# main.net
KiCad netlist of a schematic drawn in Altium Designer
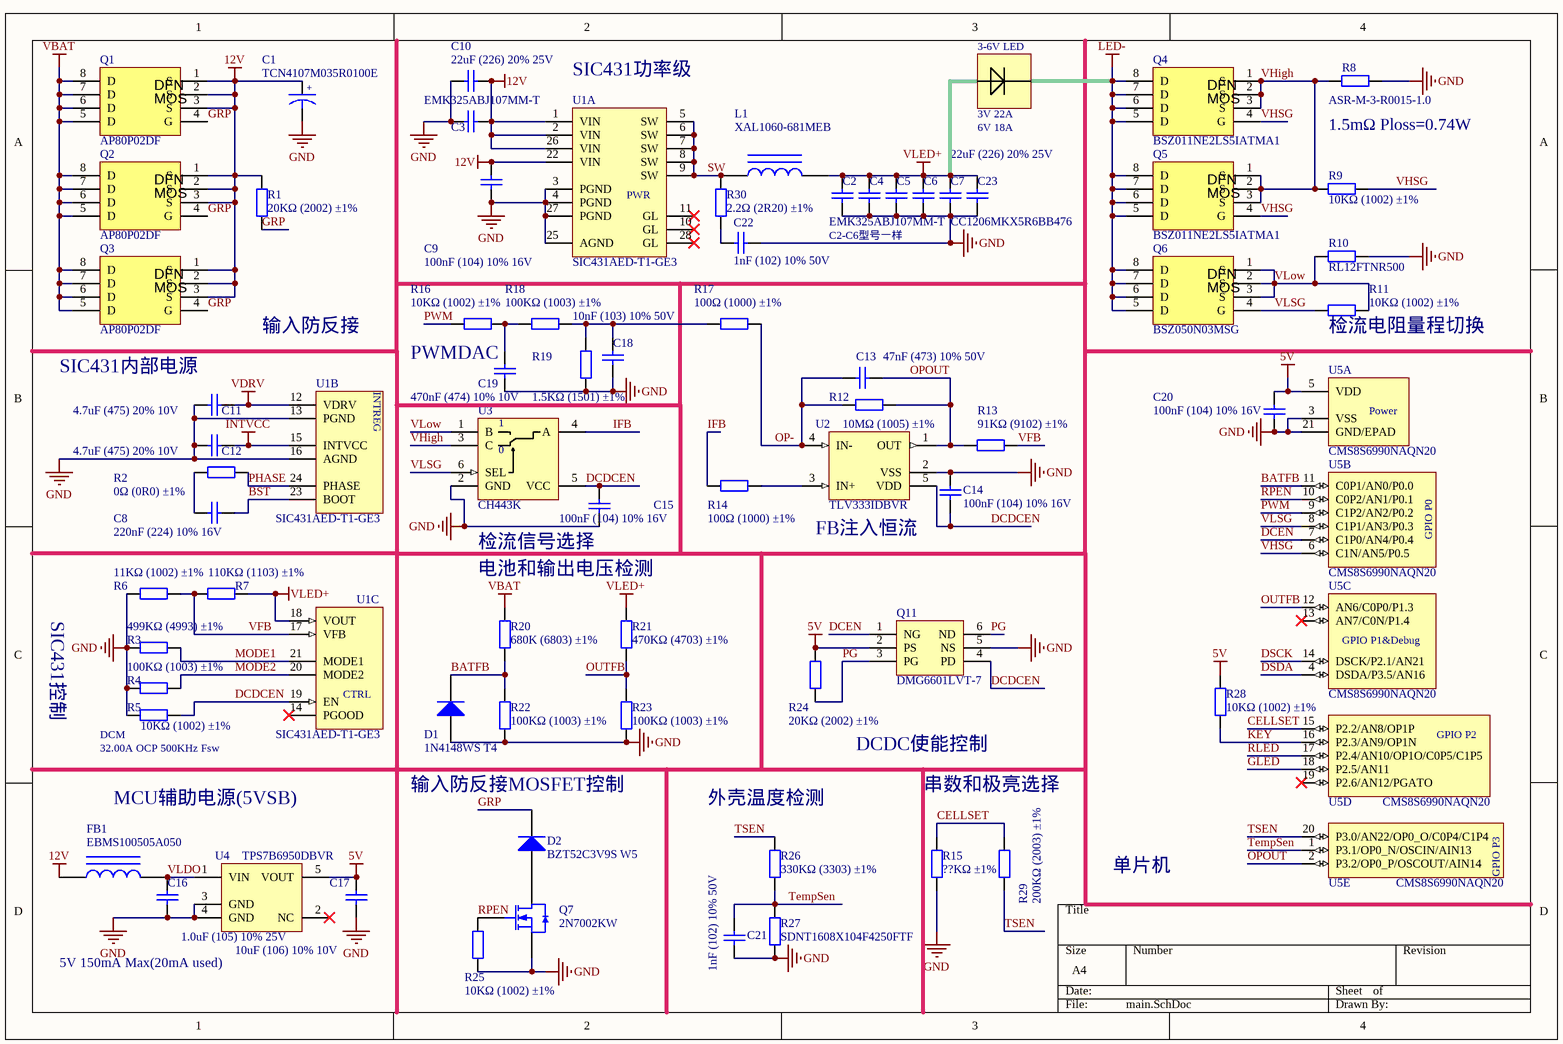
[diagram p0: main.SchDoc]

(export (version "E")
  (design (tool "Eeschema 10.0.6"))
  (components
    (comp (ref "C1")
      (value "TCN4107M035R0100E")
      (footprint "TCN4")
      (description "京瓷/AVX 贴片聚合物钽电容器 35V 100uF ±20% 2924 ESR=100mΩ")
      (libsource (lib "山猫的集成库20190318") (part "CAP2"))
    )
    (comp (ref "C2")
      (value "EMK325ABJ107MM-T")
      (footprint "1210C")
      (description "1210尺寸多层陶瓷电容器(MLCC) X5R材质，16V 100uF±20%")
      (fields (field (name "PUBLISHER") "Altium Limited"))
      (libsource (lib "山猫的集成库20190318") (part "Cap"))
    )
    (comp (ref "C3")
      (value "EMK325ABJ107MM-T")
      (footprint "1210C")
      (description "1210尺寸多层陶瓷电容器(MLCC) X5R材质，16V 100uF±20%")
      (fields (field (name "PUBLISHER") "Altium Limited"))
      (libsource (lib "山猫的集成库20190318") (part "Cap"))
    )
    (comp (ref "C4")
      (value "EMK325ABJ107MM-T")
      (footprint "1210C")
      (description "1210尺寸多层陶瓷电容器(MLCC) X5R材质，16V 100uF±20%")
      (fields (field (name "PUBLISHER") "Altium Limited"))
      (libsource (lib "山猫的集成库20190318") (part "Cap"))
    )
    (comp (ref "C5")
      (value "EMK325ABJ107MM-T")
      (footprint "1210C")
      (description "1210尺寸多层陶瓷电容器(MLCC) X5R材质，16V 100uF±20%")
      (fields (field (name "PUBLISHER") "Altium Limited"))
      (libsource (lib "山猫的集成库20190318") (part "Cap"))
    )
    (comp (ref "C6")
      (value "EMK325ABJ107MM-T")
      (footprint "1210C")
      (description "1210尺寸多层陶瓷电容器(MLCC) X5R材质，16V 100uF±20%")
      (fields (field (name "PUBLISHER") "Altium Limited"))
      (libsource (lib "山猫的集成库20190318") (part "Cap"))
    )
    (comp (ref "C7")
      (value "22uF (226) 20% 25V")
      (footprint "0805_C")
      (description "贴片电容")
      (libsource (lib "Miscellaneous Devices LC") (part "0805 22uF (226) 20% 25V"))
    )
    (comp (ref "C8")
      (value "220nF (224) 10% 16V")
      (footprint "0402_C")
      (description "贴片电容")
      (libsource (lib "Miscellaneous Devices LC") (part "0402 220nF (224) 10% 16V"))
    )
    (comp (ref "C9")
      (value "100nF (104) 10% 16V")
      (footprint "0402_C")
      (description "贴片电容")
      (libsource (lib "Miscellaneous Devices LC") (part "0402 100nF (104) 10% 16V"))
    )
    (comp (ref "C10")
      (value "22uF (226) 20% 25V")
      (footprint "0805_C")
      (description "贴片电容")
      (libsource (lib "Miscellaneous Devices LC") (part "0805 22uF (226) 20% 25V"))
    )
    (comp (ref "C11")
      (value "4.7uF (475) 20% 10V")
      (footprint "0402_C")
      (description "贴片电容")
      (libsource (lib "Miscellaneous Devices LC") (part "0402 4.7uF (475) 20% 10V"))
    )
    (comp (ref "C12")
      (value "4.7uF (475) 20% 10V")
      (footprint "0402_C")
      (description "贴片电容")
      (libsource (lib "Miscellaneous Devices LC") (part "0402 4.7uF (475) 20% 10V"))
    )
    (comp (ref "C13")
      (value "47nF (473) 10% 50V")
      (footprint "0402_C")
      (description "贴片电容")
      (libsource (lib "Miscellaneous Devices LC") (part "0402 100nF (104) 10% 16V"))
    )
    (comp (ref "C14")
      (value "100nF (104) 10% 16V")
      (footprint "0402_C")
      (description "贴片电容")
      (libsource (lib "Miscellaneous Devices LC") (part "0402 100nF (104) 10% 16V"))
    )
    (comp (ref "C15")
      (value "100nF (104) 10% 16V")
      (footprint "0402_C")
      (description "贴片电容")
      (libsource (lib "Miscellaneous Devices LC") (part "0402 100nF (104) 10% 16V"))
    )
    (comp (ref "C16")
      (value "1.0uF (105) 10% 25V")
      (footprint "0402_C")
      (description "贴片电容")
      (libsource (lib "Miscellaneous Devices LC") (part "0402 1.0uF (105) 10% 25V"))
    )
    (comp (ref "C17")
      (value "10uF (106) 10% 10V")
      (footprint "0603_C")
      (description "贴片电容")
      (libsource (lib "Miscellaneous Devices LC") (part "0603 10uF (106) 10% 10V"))
    )
    (comp (ref "C18")
      (value "10nF (103) 10% 50V")
      (footprint "0402_C")
      (description "贴片电容")
      (libsource (lib "Miscellaneous Devices LC") (part "0402 10nF (103) 10% 50V"))
    )
    (comp (ref "C19")
      (value "470nF (474) 10% 10V")
      (footprint "0402_C")
      (description "贴片电容")
      (libsource (lib "Miscellaneous Devices LC") (part "0402 470nF (474) 10% 10V"))
    )
    (comp (ref "C20")
      (value "100nF (104) 10% 16V")
      (footprint "0402_C")
      (description "贴片电容")
      (libsource (lib "Miscellaneous Devices LC") (part "0402 100nF (104) 10% 16V"))
    )
    (comp (ref "C21")
      (value "1nF (102) 10% 50V")
      (footprint "0402_C")
      (description "贴片电容")
      (libsource (lib "Miscellaneous Devices LC") (part "0402 1nF (102) 10% 50V"))
    )
    (comp (ref "C22")
      (value "1nF (102) 10% 50V")
      (footprint "0402_C")
      (description "贴片电容")
      (libsource (lib "Miscellaneous Devices LC") (part "0402 1nF (102) 10% 50V"))
    )
    (comp (ref "C23")
      (value "CC1206MKX5R6BB476")
      (footprint "1206C")
      (description "1206 MLCC电容 10V 47uF±20% X5R")
      (fields (field (name "PUBLISHER") "Altium Limited"))
      (libsource (lib "山猫的集成库20190318") (part "Cap"))
    )
    (comp (ref "D1")
      (value "1N4148WS T4")
      (footprint "SOD-323")
      (description "二极管")
      (libsource (lib "Miscellaneous Devices LC") (part "SOD-323 1N4148WS T4"))
    )
    (comp (ref "D2")
      (value "BZT52C3V9S W5")
      (footprint "SOD-323")
      (description "SOD-323封装贴片稳压二极管，3.9V 200mW")
      (libsource (lib "Miscellaneous Devices LC") (part "SOD-323 1N4148WS T4"))
    )
    (comp (ref "FB1")
      (value "EBMS100505A050")
      (footprint "0402_L")
      (description "贴片磁珠 200mA 5R±25% 100MHz")
      (libsource (lib "Miscellaneous Devices LC") (part "0402 12nH  5%"))
    )
    (comp (ref "L1")
      (value "XAL1060-681MEB")
      (footprint "XAL1010-XXXME")
      (description "Coilcraft Inductor XAL1070 Series")
      (fields (field (name "PUBLISHER") "Altium Limited"))
      (libsource (lib "Miscellaneous Devices") (part "Inductor Iron"))
    )
    (comp (ref "Q1")
      (value "AP80P02DF")
      (footprint "DFN-8_L3.0-W3.0-P0.65-BL")
      (description "永源微 PDFN3x3-8L -20V -80A 4.0mΩ P沟道MOSFET")
      (libsource (lib "custom") (part "SON/DFN5x6 MOS"))
    )
    (comp (ref "Q2")
      (value "AP80P02DF")
      (footprint "DFN-8_L3.0-W3.0-P0.65-BL")
      (description "永源微 PDFN3x3-8L -20V -80A 4.0mΩ P沟道MOSFET")
      (libsource (lib "custom") (part "SON/DFN5x6 MOS"))
    )
    (comp (ref "Q3")
      (value "AP80P02DF")
      (footprint "DFN-8_L3.0-W3.0-P0.65-BL")
      (description "永源微 PDFN3x3-8L -20V -80A 4.0mΩ P沟道MOSFET")
      (libsource (lib "custom") (part "SON/DFN5x6 MOS"))
    )
    (comp (ref "Q4")
      (value "BSZ011NE2LS5IATMA1")
      (footprint "DFN-8_L3.0-W3.0-P0.65-BL")
      (description "PDFN3x3 37nC 25V 40A 1.1mΩ OptiMOS-5 N沟道MOSFET")
      (libsource (lib "custom") (part "SON/DFN5x6 MOS"))
    )
    (comp (ref "Q5")
      (value "BSZ011NE2LS5IATMA1")
      (footprint "DFN-8_L3.0-W3.0-P0.65-BL")
      (description "PDFN3x3 37nC 25V 40A 1.1mΩ OptiMOS-5 N沟道MOSFET")
      (libsource (lib "custom") (part "SON/DFN5x6 MOS"))
    )
    (comp (ref "Q6")
      (value "BSZ050N03MSG")
      (footprint "DFN-8_L3.0-W3.0-P0.65-BL")
      (description "PDFN3x3 30V 45A 4.6mΩ OptiMOS-3 N沟道MOSFET")
      (libsource (lib "custom") (part "SON/DFN5x6 MOS"))
    )
    (comp (ref "Q7")
      (value "2N7002KW")
      (footprint "SC70-3")
      (description "单N沟道MOSFET(场效应管)")
      (libsource (lib "Miscellaneous Devices LC") (part "2N7002 7002"))
    )
    (comp (ref "Q11")
      (value "DMG6601LVT-7")
      (footprint "SOT95P245X110-6N")
      (description "SOT23-6 N+P Ch. MOSFET")
      (libsource (lib "custom") (part "DMG6601LVT"))
    )
    (comp (ref "R1")
      (value "20KΩ (2002) ±1%")
      (footprint "0402_R")
      (description "贴片电阻")
      (libsource (lib "Miscellaneous Devices LC") (part "0402 20KΩ (2002) 1%"))
    )
    (comp (ref "R2")
      (value "0Ω (0R0) ±1%")
      (footprint "0402_R")
      (description "贴片电阻")
      (libsource (lib "Miscellaneous Devices LC") (part "0402 0Ω (0R0) 1%"))
    )
    (comp (ref "R3")
      (value "499KΩ (4993) ±1%")
      (footprint "0402_R")
      (description "贴片电阻")
      (libsource (lib "") (part "0402 100KΩ (1003) 1%_1"))
    )
    (comp (ref "R4")
      (value "100KΩ (1003) ±1%")
      (footprint "0402_R")
      (description "贴片电阻")
      (libsource (lib "") (part "0402 100KΩ (1003) 1%_1"))
    )
    (comp (ref "R5")
      (value "10KΩ (1002) ±1%")
      (footprint "0402_R")
      (description "贴片电阻")
      (libsource (lib "Miscellaneous Devices LC") (part "0402 10KΩ (1002) 1%"))
    )
    (comp (ref "R6")
      (value "11KΩ (1002) ±1%")
      (footprint "0402_R")
      (description "贴片电阻")
      (libsource (lib "") (part "0402 10KΩ (1002) 1%_1"))
    )
    (comp (ref "R7")
      (value "110KΩ (1103) ±1%")
      (footprint "0402_R")
      (description "贴片电阻")
      (libsource (lib "") (part "0402 10KΩ (1002) 1%_1"))
    )
    (comp (ref "R8")
      (value "ASR-M-3-R0015-1.0")
      (footprint "2512")
      (description "深圳华讯高科精密检流电阻，2512 1.5mΩ±1% 卡玛材质 <50ppm/K P70℃=3W")
      (fields (field (name "PUBLISHER") "Altium Limited"))
      (libsource (lib "山猫的集成库20190318") (part "Res"))
    )
    (comp (ref "R9")
      (value "10KΩ (1002) ±1%")
      (footprint "0402_R")
      (description "贴片电阻")
      (libsource (lib "Miscellaneous Devices LC") (part "0402 10KΩ (1002) 1%"))
    )
    (comp (ref "R10")
      (value "RL12FTNR500")
      (footprint "1206R")
      (description "1206厚膜采样电阻 0.5Ω ±1% 1/2W")
      (fields (field (name "PUBLISHER") "Altium Limited"))
      (libsource (lib "山猫的集成库20190318") (part "Res"))
    )
    (comp (ref "R11")
      (value "10KΩ (1002) ±1%")
      (footprint "0402_R")
      (description "贴片电阻")
      (libsource (lib "Miscellaneous Devices LC") (part "0402 10KΩ (1002) 1%"))
    )
    (comp (ref "R12")
      (value "10MΩ (1005) ±1%")
      (footprint "0402_R")
      (description "贴片电阻")
      (libsource (lib "Miscellaneous Devices LC") (part "0402 1MΩ (1004) 1%"))
    )
    (comp (ref "R13")
      (value "91KΩ (9102) ±1%")
      (footprint "0402_R")
      (description "贴片电阻")
      (libsource (lib "") (part "0402 100KΩ (1003) 1%_1"))
    )
    (comp (ref "R14")
      (value "100Ω (1000) ±1%")
      (footprint "0402_R")
      (description "贴片电阻")
      (libsource (lib "Miscellaneous Devices LC") (part "0402 470Ω (4700) 1%"))
    )
    (comp (ref "R15")
      (value "??KΩ ±1%")
      (footprint "0603_R")
      (description "贴片电阻")
      (libsource (lib "Miscellaneous Devices LC") (part "0603 10KΩ (1002) 1%"))
    )
    (comp (ref "R16")
      (value "10KΩ (1002) ±1%")
      (footprint "0402_R")
      (description "贴片电阻")
      (libsource (lib "Miscellaneous Devices LC") (part "0402 10KΩ (1002) 1%"))
    )
    (comp (ref "R17")
      (value "100Ω (1000) ±1%")
      (footprint "0402_R")
      (description "贴片电阻")
      (libsource (lib "Miscellaneous Devices LC") (part "0402 470Ω (4700) 1%"))
    )
    (comp (ref "R18")
      (value "100KΩ (1003) ±1%")
      (footprint "0402_R")
      (description "贴片电阻")
      (libsource (lib "") (part "0402 100KΩ (1003) 1%_1"))
    )
    (comp (ref "R19")
      (value "1.5KΩ (1501) ±1%")
      (footprint "0402_R")
      (description "贴片电阻")
      (libsource (lib "Miscellaneous Devices LC") (part "0402 1.5KΩ (1501) 1%"))
    )
    (comp (ref "R20")
      (value "680K (6803) ±1%")
      (footprint "0402_R")
      (description "贴片电阻")
      (libsource (lib "Miscellaneous Devices LC") (part "0402 680Ω (6800) 1%"))
    )
    (comp (ref "R21")
      (value "470KΩ (4703) ±1%")
      (footprint "0402_R")
      (description "贴片电阻")
      (libsource (lib "Miscellaneous Devices LC") (part "0402 470KΩ (4703) 1%"))
    )
    (comp (ref "R22")
      (value "100KΩ (1003) ±1%")
      (footprint "0402_R")
      (description "贴片电阻")
      (libsource (lib "Miscellaneous Devices LC") (part "0402 100KΩ (1003) 1%"))
    )
    (comp (ref "R23")
      (value "100KΩ (1003) ±1%")
      (footprint "0402_R")
      (description "贴片电阻")
      (libsource (lib "Miscellaneous Devices LC") (part "0402 100KΩ (1003) 1%"))
    )
    (comp (ref "R24")
      (value "20KΩ (2002) ±1%")
      (footprint "0402_R")
      (description "贴片电阻")
      (libsource (lib "Miscellaneous Devices LC") (part "0402 20KΩ (2002) 1%"))
    )
    (comp (ref "R25")
      (value "10KΩ (1002) ±1%")
      (footprint "0402_R")
      (description "贴片电阻")
      (libsource (lib "") (part "0402 10KΩ (1002) 1%_2"))
    )
    (comp (ref "R26")
      (value "330KΩ (3303) ±1%")
      (footprint "0402_R")
      (description "贴片电阻")
      (libsource (lib "Miscellaneous Devices LC") (part "0402 330KΩ (3303) 1%"))
    )
    (comp (ref "R27")
      (value "SDNT1608X104F4250FTF")
      (footprint "0603_R")
      (description "0603贴片NTC热敏电阻，100KΩ (1003) ±1% B4250")
      (libsource (lib "Miscellaneous Devices LC") (part "0603 100KΩ (1003) 1%"))
    )
    (comp (ref "R28")
      (value "10KΩ (1002) ±1%")
      (footprint "0402_R")
      (description "贴片电阻")
      (libsource (lib "") (part "0402 10KΩ (1002) 1%_2"))
    )
    (comp (ref "R29")
      (value "200KΩ (2003) ±1%")
      (footprint "0402_R")
      (description "贴片电阻")
      (libsource (lib "Miscellaneous Devices LC") (part "0402 100KΩ (1003) 1%"))
    )
    (comp (ref "R30")
      (value "2.2Ω (2R20) ±1%")
      (footprint "0805_R")
      (description "贴片电阻")
      (libsource (lib "Miscellaneous Devices LC") (part "0805 1Ω (1R00) 1%"))
    )
    (comp (ref "U1")
      (value "SIC431AED-T1-GE3")
      (footprint "QFN_ED-T1-GE3_VIS")
      (description "3 to 24V Input 24A MicroBuck DCDC Converter with bulit-in MOSFET")
      (libsource (lib "custom") (part "SIC431AED-T1-GE3"))
    )
    (comp (ref "U2")
      (value "TLV333IDBVR")
      (footprint "SOT95P245X110-5N")
      (description "低噪声轨到轨输入输出精密运放 350Khz")
      (libsource (lib "custom") (part "TLV333IDBVR"))
    )
    (comp (ref "U3")
      (value "CH443K")
      (footprint "SC70-6")
      (description "Low-Voltage Analog Switch SPDT,1.8-5V Power")
      (libsource (lib "custom") (part "NC7SB3157P6X"))
    )
    (comp (ref "U4")
      (value "TPS7B6950DBVR")
      (footprint "SOT95P245X110-5N")
      (description "150mA 40V max input Ultra low Iq LDO,fixed 5V output")
      (libsource (lib "custom") (part "TPS7B6933DBVR"))
    )
    (comp (ref "U5")
      (value "CMS8S6990NAQN20")
      (footprint "QFN40P300X300X800_HS-21N")
      (description "增强型闪存1T 8051单片机，16KB Flash 256+1K XRAM")
      (libsource (lib "custom") (part "CM8S6990NA-QFN20"))
    )
  )
  (nets
    (net (code "1") (name "/BATFB") (class "Default")
      (node (ref "D1") (pin "2") (pinfunction "K_2") (pintype "passive"))
      (node (ref "R20") (pin "1") (pinfunction "1_1") (pintype "passive"))
      (node (ref "R22") (pin "2") (pinfunction "2_2") (pintype "passive"))
      (node (ref "U5") (pin "11") (pinfunction "C0P1/AN0/P0.0_11") (pintype "bidirectional"))
    )
    (net (code "2") (name "/BST") (class "Default")
      (node (ref "C8") (pin "2") (pinfunction "2_2") (pintype "passive"))
      (node (ref "U1") (pin "23") (pinfunction "BOOT_23") (pintype "power_in"))
    )
    (net (code "3") (name "/CELLSET") (class "Default")
      (node (ref "R15") (pin "2") (pinfunction "2_2") (pintype "passive"))
      (node (ref "R29") (pin "2") (pinfunction "2_2") (pintype "passive"))
      (node (ref "U5") (pin "15") (pinfunction "P2.2/AN8/OP1P_15") (pintype "bidirectional"))
    )
    (net (code "4") (name "/DCDCEN") (class "Default")
      (node (ref "C14") (pin "1") (pinfunction "1_1") (pintype "passive"))
      (node (ref "C15") (pin "2") (pinfunction "2_2") (pintype "passive"))
      (node (ref "Q11") (pin "4") (pinfunction "PD_4") (pintype "passive"))
      (node (ref "R5") (pin "2") (pinfunction "2_2") (pintype "passive"))
      (node (ref "U1") (pin "19") (pinfunction "EN_19") (pintype "input"))
      (node (ref "U2") (pin "5") (pinfunction "VDD_5") (pintype "power_in"))
      (node (ref "U3") (pin "5") (pinfunction "VCC_5") (pintype "power_in"))
    )
    (net (code "5") (name "/DCEN") (class "Default")
      (node (ref "Q11") (pin "1") (pinfunction "NG_1") (pintype "passive"))
      (node (ref "U5") (pin "7") (pinfunction "C1P0/AN4/P0.4_7") (pintype "bidirectional"))
    )
    (net (code "6") (name "/DSCK") (class "Default")
      (node (ref "U5") (pin "14") (pinfunction "DSCK/P2.1/AN21_14") (pintype "bidirectional"))
    )
    (net (code "7") (name "/DSDA") (class "Default")
      (node (ref "U5") (pin "4") (pinfunction "DSDA/P3.5/AN16_4") (pintype "bidirectional"))
    )
    (net (code "8") (name "/GLED") (class "Default")
      (node (ref "U5") (pin "18") (pinfunction "P2.5/AN11_18") (pintype "bidirectional"))
    )
    (net (code "9") (name "/GRP") (class "Default")
      (node (ref "D2") (pin "2") (pinfunction "K_2") (pintype "passive"))
      (node (ref "Q1") (pin "4") (pinfunction "G_4") (pintype "passive"))
      (node (ref "Q2") (pin "4") (pinfunction "G_4") (pintype "passive"))
      (node (ref "Q3") (pin "4") (pinfunction "G_4") (pintype "passive"))
      (node (ref "R1") (pin "1") (pinfunction "1_1") (pintype "passive"))
    )
    (net (code "10") (name "/IFB") (class "Default")
      (node (ref "R14") (pin "1") (pinfunction "1_1") (pintype "passive"))
      (node (ref "U3") (pin "4") (pinfunction "A_4") (pintype "passive"))
    )
    (net (code "11") (name "/KEY") (class "Default")
      (node (ref "R28") (pin "1") (pinfunction "1_1") (pintype "passive"))
      (node (ref "U5") (pin "16") (pinfunction "P2.3/AN9/OP1N_16") (pintype "bidirectional"))
    )
    (net (code "12") (name "/MODE1") (class "Default")
      (node (ref "R3") (pin "2") (pinfunction "2_2") (pintype "passive"))
      (node (ref "U1") (pin "21") (pinfunction "MODE1_21") (pintype "passive"))
    )
    (net (code "13") (name "/MODE2") (class "Default")
      (node (ref "R4") (pin "2") (pinfunction "2_2") (pintype "passive"))
      (node (ref "U1") (pin "20") (pinfunction "MODE2_20") (pintype "passive"))
    )
    (net (code "14") (name "/OP-") (class "Default")
      (node (ref "C13") (pin "1") (pinfunction "1_1") (pintype "passive"))
      (node (ref "R12") (pin "1") (pinfunction "1_1") (pintype "passive"))
      (node (ref "R17") (pin "2") (pinfunction "2_2") (pintype "passive"))
      (node (ref "U2") (pin "4") (pinfunction "IN-_4") (pintype "input"))
    )
    (net (code "15") (name "/OPOUT") (class "Default")
      (node (ref "C13") (pin "2") (pinfunction "2_2") (pintype "passive"))
      (node (ref "R12") (pin "2") (pinfunction "2_2") (pintype "passive"))
      (node (ref "R13") (pin "1") (pinfunction "1_1") (pintype "passive"))
      (node (ref "U2") (pin "1") (pinfunction "OUT_1") (pintype "output"))
      (node (ref "U5") (pin "2") (pinfunction "P3.2/OP0_P/OSCOUT/AIN14_2") (pintype "bidirectional"))
    )
    (net (code "16") (name "/OUTFB") (class "Default")
      (node (ref "R21") (pin "1") (pinfunction "1_1") (pintype "passive"))
      (node (ref "R23") (pin "2") (pinfunction "2_2") (pintype "passive"))
      (node (ref "U5") (pin "12") (pinfunction "AN6/C0P0/P1.3_12") (pintype "bidirectional"))
    )
    (net (code "17") (name "/PG") (class "Default")
      (node (ref "Q11") (pin "3") (pinfunction "PG_3") (pintype "passive"))
      (node (ref "Q11") (pin "6") (pinfunction "ND_6") (pintype "passive"))
      (node (ref "R24") (pin "1") (pinfunction "1_1") (pintype "passive"))
    )
    (net (code "18") (name "/PHASE") (class "Default")
      (node (ref "R2") (pin "2") (pinfunction "2_2") (pintype "passive"))
      (node (ref "U1") (pin "24") (pinfunction "PHASE_24") (pintype "power_in"))
    )
    (net (code "19") (name "/PWM") (class "Default")
      (node (ref "R16") (pin "1") (pinfunction "1_1") (pintype "passive"))
      (node (ref "U5") (pin "9") (pinfunction "C1P2/AN2/P0.2_9") (pintype "bidirectional"))
    )
    (net (code "20") (name "/RLED") (class "Default")
      (node (ref "U5") (pin "17") (pinfunction "P2.4/AN10/OP1O/C0P5/C1P5_17") (pintype "bidirectional"))
    )
    (net (code "21") (name "/RPEN") (class "Default")
      (node (ref "Q7") (pin "1") (pinfunction "G_1") (pintype "passive"))
      (node (ref "R25") (pin "2") (pinfunction "2_2") (pintype "passive"))
      (node (ref "U5") (pin "10") (pinfunction "C0P2/AN1/P0.1_10") (pintype "bidirectional"))
    )
    (net (code "22") (name "/SW") (class "Default")
      (node (ref "L1") (pin "1") (pinfunction "1_1") (pintype "passive"))
      (node (ref "R30") (pin "2") (pinfunction "2_2") (pintype "passive"))
      (node (ref "U1") (pin "5") (pinfunction "SW_5") (pintype "power_in"))
      (node (ref "U1") (pin "6") (pinfunction "SW_6") (pintype "power_in"))
      (node (ref "U1") (pin "7") (pinfunction "SW_7") (pintype "power_in"))
      (node (ref "U1") (pin "8") (pinfunction "SW_8") (pintype "power_in"))
      (node (ref "U1") (pin "9") (pinfunction "SW_9") (pintype "power_in"))
    )
    (net (code "23") (name "/TSEN") (class "Default")
      (node (ref "R26") (pin "2") (pinfunction "2_2") (pintype "passive"))
      (node (ref "R29") (pin "1") (pinfunction "1_1") (pintype "passive"))
      (node (ref "U5") (pin "20") (pinfunction "P3.0/AN22/OP0_O/C0P4/C1P4_20") (pintype "bidirectional"))
    )
    (net (code "24") (name "/TempSen") (class "Default")
      (node (ref "C21") (pin "2") (pinfunction "2_2") (pintype "passive"))
      (node (ref "R26") (pin "1") (pinfunction "1_1") (pintype "passive"))
      (node (ref "R27") (pin "1") (pinfunction "1_1") (pintype "passive"))
      (node (ref "U5") (pin "1") (pinfunction "P3.1/OP0_N/OSCIN/AIN13_1") (pintype "bidirectional"))
    )
    (net (code "25") (name "/VFB") (class "Default")
      (node (ref "R13") (pin "2") (pinfunction "2_2") (pintype "passive"))
      (node (ref "R6") (pin "1") (pinfunction "1_1") (pintype "passive"))
      (node (ref "R7") (pin "2") (pinfunction "2_2") (pintype "passive"))
      (node (ref "U1") (pin "17") (pinfunction "VFB_17") (pintype "input"))
    )
    (net (code "26") (name "/VHSG") (class "Default")
      (node (ref "Q4") (pin "4") (pinfunction "G_4") (pintype "passive"))
      (node (ref "Q5") (pin "4") (pinfunction "G_4") (pintype "passive"))
      (node (ref "R9") (pin "2") (pinfunction "2_2") (pintype "passive"))
      (node (ref "U5") (pin "6") (pinfunction "C1N/AN5/P0.5_6") (pintype "bidirectional"))
    )
    (net (code "27") (name "/VHigh") (class "Default")
      (node (ref "Q4") (pin "1") (pinfunction "S_1") (pintype "passive"))
      (node (ref "Q4") (pin "2") (pinfunction "S_2") (pintype "passive"))
      (node (ref "Q4") (pin "3") (pinfunction "S_3") (pintype "passive"))
      (node (ref "Q5") (pin "1") (pinfunction "S_1") (pintype "passive"))
      (node (ref "Q5") (pin "2") (pinfunction "S_2") (pintype "passive"))
      (node (ref "Q5") (pin "3") (pinfunction "S_3") (pintype "passive"))
      (node (ref "R8") (pin "2") (pinfunction "2_2") (pintype "passive"))
      (node (ref "R9") (pin "1") (pinfunction "1_1") (pintype "passive"))
      (node (ref "U3") (pin "3") (pinfunction "C_3") (pintype "passive"))
    )
    (net (code "28") (name "/VLDO") (class "Default")
      (node (ref "C16") (pin "2") (pinfunction "2_2") (pintype "passive"))
      (node (ref "FB1") (pin "2") (pinfunction "2_2") (pintype "passive"))
      (node (ref "U4") (pin "1") (pinfunction "VIN_1") (pintype "power_in"))
    )
    (net (code "29") (name "/VLSG") (class "Default")
      (node (ref "Q6") (pin "4") (pinfunction "G_4") (pintype "passive"))
      (node (ref "R11") (pin "1") (pinfunction "1_1") (pintype "passive"))
      (node (ref "U3") (pin "6") (pinfunction "SEL_6") (pintype "input"))
      (node (ref "U5") (pin "8") (pinfunction "C1P1/AN3/P0.3_8") (pintype "bidirectional"))
    )
    (net (code "30") (name "/VLow") (class "Default")
      (node (ref "Q6") (pin "1") (pinfunction "S_1") (pintype "passive"))
      (node (ref "Q6") (pin "2") (pinfunction "S_2") (pintype "passive"))
      (node (ref "Q6") (pin "3") (pinfunction "S_3") (pintype "passive"))
      (node (ref "R10") (pin "2") (pinfunction "2_2") (pintype "passive"))
      (node (ref "R11") (pin "2") (pinfunction "2_2") (pintype "passive"))
      (node (ref "U3") (pin "1") (pinfunction "B_1") (pintype "passive"))
    )
    (net (code "31") (name "5V") (class "Default")
      (node (ref "C17") (pin "2") (pinfunction "2_2") (pintype "passive"))
      (node (ref "C20") (pin "2") (pinfunction "2_2") (pintype "passive"))
      (node (ref "Q11") (pin "2") (pinfunction "PS_2") (pintype "passive"))
      (node (ref "R24") (pin "2") (pinfunction "2_2") (pintype "passive"))
      (node (ref "R28") (pin "2") (pinfunction "2_2") (pintype "passive"))
      (node (ref "U4") (pin "5") (pinfunction "VOUT_5") (pintype "power_in"))
      (node (ref "U5") (pin "5") (pinfunction "VDD_5") (pintype "power_in"))
    )
    (net (code "32") (name "12V") (class "Default")
      (node (ref "C1") (pin "1") (pinfunction "1_1") (pintype "passive"))
      (node (ref "C10") (pin "2") (pinfunction "2_2") (pintype "passive"))
      (node (ref "C3") (pin "2") (pinfunction "2_2") (pintype "passive"))
      (node (ref "C9") (pin "2") (pinfunction "2_2") (pintype "passive"))
      (node (ref "FB1") (pin "1") (pinfunction "1_1") (pintype "passive"))
      (node (ref "Q1") (pin "1") (pinfunction "S_1") (pintype "passive"))
      (node (ref "Q1") (pin "2") (pinfunction "S_2") (pintype "passive"))
      (node (ref "Q1") (pin "3") (pinfunction "S_3") (pintype "passive"))
      (node (ref "Q2") (pin "1") (pinfunction "S_1") (pintype "passive"))
      (node (ref "Q2") (pin "2") (pinfunction "S_2") (pintype "passive"))
      (node (ref "Q2") (pin "3") (pinfunction "S_3") (pintype "passive"))
      (node (ref "Q3") (pin "1") (pinfunction "S_1") (pintype "passive"))
      (node (ref "Q3") (pin "2") (pinfunction "S_2") (pintype "passive"))
      (node (ref "Q3") (pin "3") (pinfunction "S_3") (pintype "passive"))
      (node (ref "R1") (pin "2") (pinfunction "2_2") (pintype "passive"))
      (node (ref "U1") (pin "1") (pinfunction "VIN_1") (pintype "power_in"))
      (node (ref "U1") (pin "2") (pinfunction "VIN_2") (pintype "power_in"))
      (node (ref "U1") (pin "22") (pinfunction "VIN_22") (pintype "power_in"))
      (node (ref "U1") (pin "26") (pinfunction "VIN_26") (pintype "power_in"))
    )
    (net (code "33") (name "GND") (class "Default")
      (node (ref "C1") (pin "2") (pinfunction "2_2") (pintype "passive"))
      (node (ref "C10") (pin "1") (pinfunction "1_1") (pintype "passive"))
      (node (ref "C11") (pin "1") (pinfunction "1_1") (pintype "passive"))
      (node (ref "C12") (pin "1") (pinfunction "1_1") (pintype "passive"))
      (node (ref "C14") (pin "2") (pinfunction "2_2") (pintype "passive"))
      (node (ref "C15") (pin "1") (pinfunction "1_1") (pintype "passive"))
      (node (ref "C16") (pin "1") (pinfunction "1_1") (pintype "passive"))
      (node (ref "C17") (pin "1") (pinfunction "1_1") (pintype "passive"))
      (node (ref "C18") (pin "1") (pinfunction "1_1") (pintype "passive"))
      (node (ref "C19") (pin "1") (pinfunction "1_1") (pintype "passive"))
      (node (ref "C2") (pin "1") (pinfunction "1_1") (pintype "passive"))
      (node (ref "C20") (pin "1") (pinfunction "1_1") (pintype "passive"))
      (node (ref "C21") (pin "1") (pinfunction "1_1") (pintype "passive"))
      (node (ref "C22") (pin "1") (pinfunction "1_1") (pintype "passive"))
      (node (ref "C23") (pin "1") (pinfunction "1_1") (pintype "passive"))
      (node (ref "C3") (pin "1") (pinfunction "1_1") (pintype "passive"))
      (node (ref "C4") (pin "1") (pinfunction "1_1") (pintype "passive"))
      (node (ref "C5") (pin "1") (pinfunction "1_1") (pintype "passive"))
      (node (ref "C6") (pin "1") (pinfunction "1_1") (pintype "passive"))
      (node (ref "C7") (pin "1") (pinfunction "1_1") (pintype "passive"))
      (node (ref "C9") (pin "1") (pinfunction "1_1") (pintype "passive"))
      (node (ref "D1") (pin "1") (pinfunction "A_1") (pintype "passive"))
      (node (ref "Q11") (pin "5") (pinfunction "NS_5") (pintype "passive"))
      (node (ref "Q7") (pin "2") (pinfunction "S_2") (pintype "passive"))
      (node (ref "R10") (pin "1") (pinfunction "1_1") (pintype "passive"))
      (node (ref "R15") (pin "1") (pinfunction "1_1") (pintype "passive"))
      (node (ref "R19") (pin "1") (pinfunction "1_1") (pintype "passive"))
      (node (ref "R22") (pin "1") (pinfunction "1_1") (pintype "passive"))
      (node (ref "R23") (pin "1") (pinfunction "1_1") (pintype "passive"))
      (node (ref "R25") (pin "1") (pinfunction "1_1") (pintype "passive"))
      (node (ref "R27") (pin "2") (pinfunction "2_2") (pintype "passive"))
      (node (ref "R3") (pin "1") (pinfunction "1_1") (pintype "passive"))
      (node (ref "R4") (pin "1") (pinfunction "1_1") (pintype "passive"))
      (node (ref "R5") (pin "1") (pinfunction "1_1") (pintype "passive"))
      (node (ref "R6") (pin "2") (pinfunction "2_2") (pintype "passive"))
      (node (ref "R8") (pin "1") (pinfunction "1_1") (pintype "passive"))
      (node (ref "U1") (pin "13") (pinfunction "PGND_13") (pintype "power_in"))
      (node (ref "U1") (pin "16") (pinfunction "AGND_16") (pintype "power_in"))
      (node (ref "U1") (pin "25") (pinfunction "AGND_25") (pintype "power_in"))
      (node (ref "U1") (pin "27") (pinfunction "PGND_27") (pintype "power_in"))
      (node (ref "U1") (pin "3") (pinfunction "PGND_3") (pintype "power_in"))
      (node (ref "U1") (pin "4") (pinfunction "PGND_4") (pintype "power_in"))
      (node (ref "U2") (pin "2") (pinfunction "VSS_2") (pintype "power_in"))
      (node (ref "U3") (pin "2") (pinfunction "GND_2") (pintype "power_in"))
      (node (ref "U4") (pin "3") (pinfunction "GND_3") (pintype "power_in"))
      (node (ref "U4") (pin "4") (pinfunction "GND_4") (pintype "power_in"))
      (node (ref "U5") (pin "21") (pinfunction "GND/EPAD_21") (pintype "power_in"))
      (node (ref "U5") (pin "3") (pinfunction "VSS_3") (pintype "power_in"))
    )
    (net (code "34") (name "INTVCC") (class "Default")
      (node (ref "C12") (pin "2") (pinfunction "2_2") (pintype "passive"))
      (node (ref "U1") (pin "15") (pinfunction "INTVCC_15") (pintype "power_in"))
    )
    (net (code "35") (name "LED-") (class "Default")
      (node (ref "Q4") (pin "5") (pinfunction "D_5") (pintype "passive"))
      (node (ref "Q4") (pin "6") (pinfunction "D_6") (pintype "passive"))
      (node (ref "Q4") (pin "7") (pinfunction "D_7") (pintype "passive"))
      (node (ref "Q4") (pin "8") (pinfunction "D_8") (pintype "passive"))
      (node (ref "Q5") (pin "5") (pinfunction "D_5") (pintype "passive"))
      (node (ref "Q5") (pin "6") (pinfunction "D_6") (pintype "passive"))
      (node (ref "Q5") (pin "7") (pinfunction "D_7") (pintype "passive"))
      (node (ref "Q5") (pin "8") (pinfunction "D_8") (pintype "passive"))
      (node (ref "Q6") (pin "5") (pinfunction "D_5") (pintype "passive"))
      (node (ref "Q6") (pin "6") (pinfunction "D_6") (pintype "passive"))
      (node (ref "Q6") (pin "7") (pinfunction "D_7") (pintype "passive"))
      (node (ref "Q6") (pin "8") (pinfunction "D_8") (pintype "passive"))
    )
    (net (code "36") (name "Net-(C8-Pad1)") (class "Default")
      (node (ref "C8") (pin "1") (pinfunction "1_1") (pintype "passive"))
      (node (ref "R2") (pin "1") (pinfunction "1_1") (pintype "passive"))
    )
    (net (code "37") (name "Net-(C18-Pad2)") (class "Default")
      (node (ref "C18") (pin "2") (pinfunction "2_2") (pintype "passive"))
      (node (ref "R17") (pin "1") (pinfunction "1_1") (pintype "passive"))
      (node (ref "R18") (pin "2") (pinfunction "2_2") (pintype "passive"))
      (node (ref "R19") (pin "2") (pinfunction "2_2") (pintype "passive"))
    )
    (net (code "38") (name "Net-(C19-Pad2)") (class "Default")
      (node (ref "C19") (pin "2") (pinfunction "2_2") (pintype "passive"))
      (node (ref "R16") (pin "2") (pinfunction "2_2") (pintype "passive"))
      (node (ref "R18") (pin "1") (pinfunction "1_1") (pintype "passive"))
    )
    (net (code "39") (name "Net-(C22-Pad2)") (class "Default")
      (node (ref "C22") (pin "2") (pinfunction "2_2") (pintype "passive"))
      (node (ref "R30") (pin "1") (pinfunction "1_1") (pintype "passive"))
    )
    (net (code "40") (name "Net-(D2-A)") (class "Default")
      (node (ref "D2") (pin "1") (pinfunction "A_1") (pintype "passive"))
      (node (ref "Q7") (pin "3") (pinfunction "D_3") (pintype "passive"))
    )
    (net (code "41") (name "Net-(U2-IN+)") (class "Default")
      (node (ref "R14") (pin "2") (pinfunction "2_2") (pintype "passive"))
      (node (ref "U2") (pin "3") (pinfunction "IN+_3") (pintype "input"))
    )
    (net (code "42") (name "VBAT") (class "Default")
      (node (ref "Q1") (pin "5") (pinfunction "D_5") (pintype "passive"))
      (node (ref "Q1") (pin "6") (pinfunction "D_6") (pintype "passive"))
      (node (ref "Q1") (pin "7") (pinfunction "D_7") (pintype "passive"))
      (node (ref "Q1") (pin "8") (pinfunction "D_8") (pintype "passive"))
      (node (ref "Q2") (pin "5") (pinfunction "D_5") (pintype "passive"))
      (node (ref "Q2") (pin "6") (pinfunction "D_6") (pintype "passive"))
      (node (ref "Q2") (pin "7") (pinfunction "D_7") (pintype "passive"))
      (node (ref "Q2") (pin "8") (pinfunction "D_8") (pintype "passive"))
      (node (ref "Q3") (pin "5") (pinfunction "D_5") (pintype "passive"))
      (node (ref "Q3") (pin "6") (pinfunction "D_6") (pintype "passive"))
      (node (ref "Q3") (pin "7") (pinfunction "D_7") (pintype "passive"))
      (node (ref "Q3") (pin "8") (pinfunction "D_8") (pintype "passive"))
      (node (ref "R20") (pin "2") (pinfunction "2_2") (pintype "passive"))
    )
    (net (code "43") (name "VDRV") (class "Default")
      (node (ref "C11") (pin "2") (pinfunction "2_2") (pintype "passive"))
      (node (ref "U1") (pin "12") (pinfunction "VDRV_12") (pintype "power_in"))
    )
    (net (code "44") (name "VLED+") (class "Default")
      (node (ref "C2") (pin "2") (pinfunction "2_2") (pintype "passive"))
      (node (ref "C23") (pin "2") (pinfunction "2_2") (pintype "passive"))
      (node (ref "C4") (pin "2") (pinfunction "2_2") (pintype "passive"))
      (node (ref "C5") (pin "2") (pinfunction "2_2") (pintype "passive"))
      (node (ref "C6") (pin "2") (pinfunction "2_2") (pintype "passive"))
      (node (ref "C7") (pin "2") (pinfunction "2_2") (pintype "passive"))
      (node (ref "L1") (pin "2") (pinfunction "2_2") (pintype "passive"))
      (node (ref "R21") (pin "2") (pinfunction "2_2") (pintype "passive"))
      (node (ref "R7") (pin "1") (pinfunction "1_1") (pintype "passive"))
      (node (ref "U1") (pin "18") (pinfunction "VOUT_18") (pintype "input"))
    )
    (net (code "45") (name "unconnected-(U1A-GL-Pad10)") (class "Default")
      (node (ref "U1") (pin "10") (pinfunction "GL_10") (pintype "power_in+no_connect"))
    )
    (net (code "46") (name "unconnected-(U1A-GL-Pad11)") (class "Default")
      (node (ref "U1") (pin "11") (pinfunction "GL_11") (pintype "power_in+no_connect"))
    )
    (net (code "47") (name "unconnected-(U1A-GL-Pad28)") (class "Default")
      (node (ref "U1") (pin "28") (pinfunction "GL_28") (pintype "power_in+no_connect"))
    )
    (net (code "48") (name "unconnected-(U1C-PGOOD-Pad14)") (class "Default")
      (node (ref "U1") (pin "14") (pinfunction "PGOOD_14") (pintype "open_collector+no_connect"))
    )
    (net (code "49") (name "unconnected-(U4-NC-Pad2)") (class "Default")
      (node (ref "U4") (pin "2") (pinfunction "NC_2") (pintype "passive+no_connect"))
    )
    (net (code "50") (name "unconnected-(U5C-AN7{slash}C0N{slash}P1.4-Pad13)") (class "Default")
      (node (ref "U5") (pin "13") (pinfunction "AN7/C0N/P1.4_13") (pintype "bidirectional+no_connect"))
    )
    (net (code "51") (name "unconnected-(U5D-P2.6{slash}AN12{slash}PGATO-Pad19)") (class "Default")
      (node (ref "U5") (pin "19") (pinfunction "P2.6/AN12/PGATO_19") (pintype "bidirectional+no_connect"))
    )
  )
)
